# snowflake_insert.net
KiCad netlist of a schematic drawn in EAGLE
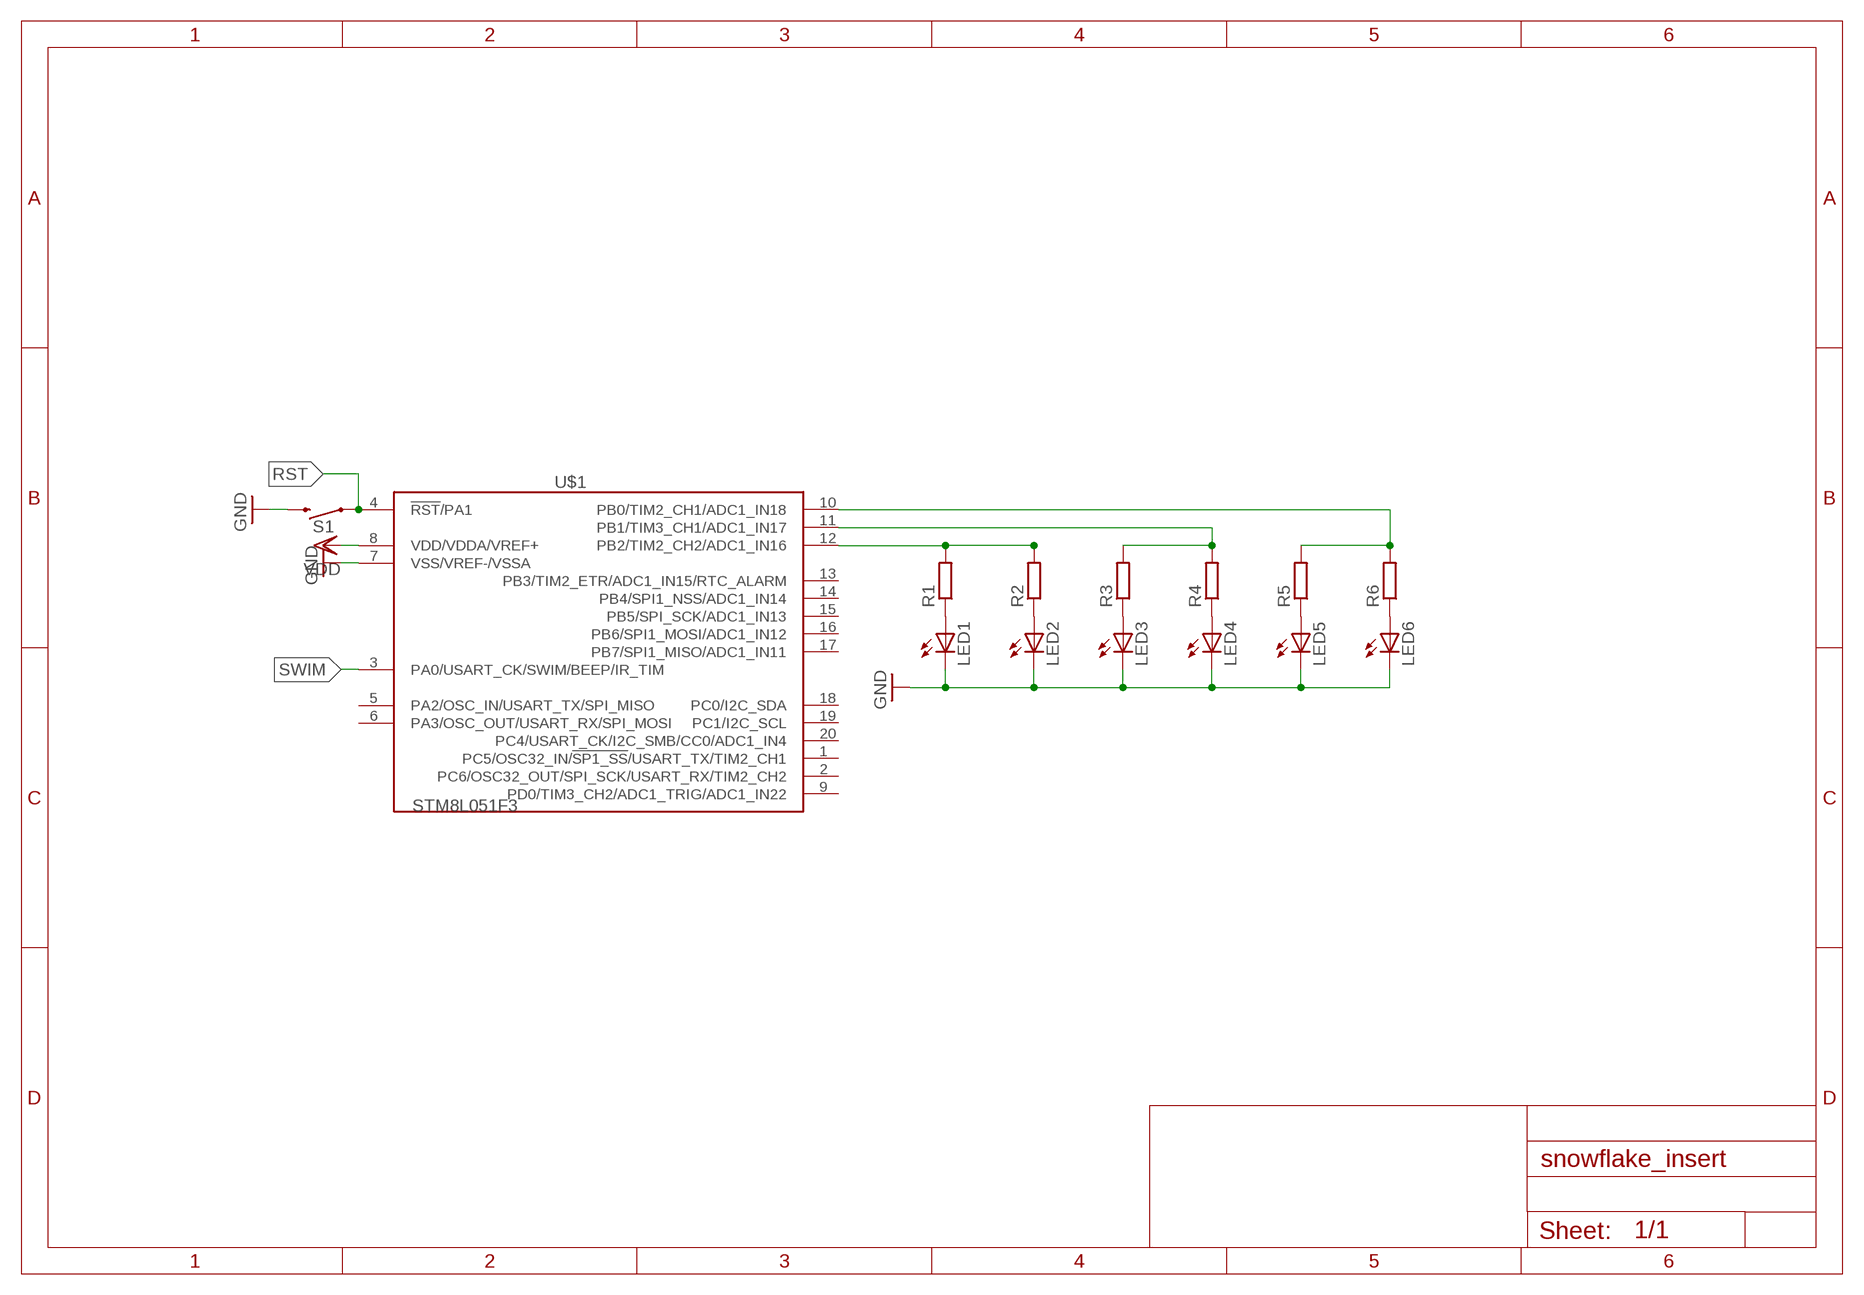
[diagram p0: schematic, sheet 1]

(export (version "E")
  (design (tool "Eeschema 10.0.6"))
  (components
    (comp (ref "LED1")
      (value "LEDSML0805")
      (footprint "eagle-import:SML0805")
      (libsource (lib "eagle-import") (part "LEDSML0805"))
    )
    (comp (ref "LED2")
      (value "LEDSML0805")
      (footprint "eagle-import:SML0805")
      (libsource (lib "eagle-import") (part "LEDSML0805"))
    )
    (comp (ref "LED3")
      (value "LEDSML0805")
      (footprint "eagle-import:SML0805")
      (libsource (lib "eagle-import") (part "LEDSML0805"))
    )
    (comp (ref "LED4")
      (value "LEDSML0805")
      (footprint "eagle-import:SML0805")
      (libsource (lib "eagle-import") (part "LEDSML0805"))
    )
    (comp (ref "LED5")
      (value "LEDSML0805")
      (footprint "eagle-import:SML0805")
      (libsource (lib "eagle-import") (part "LEDSML0805"))
    )
    (comp (ref "LED6")
      (value "LEDSML0805")
      (footprint "eagle-import:SML0805")
      (libsource (lib "eagle-import") (part "LEDSML0805"))
    )
    (comp (ref "R1")
      (value "R-EU_R0603")
      (footprint "eagle-import:R0603")
      (libsource (lib "eagle-import") (part "R-EU_R0603"))
    )
    (comp (ref "R2")
      (value "R-EU_R0603")
      (footprint "eagle-import:R0603")
      (libsource (lib "eagle-import") (part "R-EU_R0603"))
    )
    (comp (ref "R3")
      (value "R-EU_R0402")
      (footprint "eagle-import:R0402")
      (libsource (lib "eagle-import") (part "R-EU_R0402"))
    )
    (comp (ref "R4")
      (value "R-EU_R0603")
      (footprint "eagle-import:R0603")
      (libsource (lib "eagle-import") (part "R-EU_R0603"))
    )
    (comp (ref "R5")
      (value "R-EU_R0603")
      (footprint "eagle-import:R0603")
      (libsource (lib "eagle-import") (part "R-EU_R0603"))
    )
    (comp (ref "R6")
      (value "R-EU_R0603")
      (footprint "eagle-import:R0603")
      (libsource (lib "eagle-import") (part "R-EU_R0603"))
    )
    (comp (ref "S1")
      (value "MOMENTARY-SWITCH-SPST-SMD-6.0X3.5MM")
      (footprint "eagle-import:TACTILE_SWITCH_SMD_6.0X3.5MM")
      (libsource (lib "eagle-import") (part "MOMENTARY-SWITCH-SPST-SMD-6.0X3.5MM"))
    )
    (comp (ref "U$1")
      (value "STM8L051F3")
      (footprint "eagle-import:TSSOP20")
      (libsource (lib "eagle-import") (part "STM8L051F3"))
    )
  )
  (nets
    (net (code "1") (name "GND") (class "Default")
      (node (ref "LED1") (pin "C") (pinfunction "C_C") (pintype "passive"))
      (node (ref "LED2") (pin "C") (pinfunction "C_C") (pintype "passive"))
      (node (ref "LED3") (pin "C") (pinfunction "C_C") (pintype "passive"))
      (node (ref "LED4") (pin "C") (pinfunction "C_C") (pintype "passive"))
      (node (ref "LED5") (pin "C") (pinfunction "C_C") (pintype "passive"))
      (node (ref "LED6") (pin "C") (pinfunction "C_C") (pintype "passive"))
      (node (ref "S1") (pin "2") (pinfunction "2_2") (pintype "passive"))
      (node (ref "U$1") (pin "7") (pinfunction "VSS/VREF-/VSSA_7") (pintype "power_in"))
    )
    (net (code "2") (name "Net-(LED1-PadA)") (class "Default")
      (node (ref "LED1") (pin "A") (pinfunction "A_A") (pintype "passive"))
      (node (ref "R1") (pin "1") (pinfunction "1_1") (pintype "passive"))
    )
    (net (code "3") (name "Net-(LED2-PadA)") (class "Default")
      (node (ref "LED2") (pin "A") (pinfunction "A_A") (pintype "passive"))
      (node (ref "R2") (pin "1") (pinfunction "1_1") (pintype "passive"))
    )
    (net (code "4") (name "Net-(LED3-PadA)") (class "Default")
      (node (ref "LED3") (pin "A") (pinfunction "A_A") (pintype "passive"))
      (node (ref "R3") (pin "1") (pinfunction "1_1") (pintype "passive"))
    )
    (net (code "5") (name "Net-(LED4-PadA)") (class "Default")
      (node (ref "LED4") (pin "A") (pinfunction "A_A") (pintype "passive"))
      (node (ref "R4") (pin "1") (pinfunction "1_1") (pintype "passive"))
    )
    (net (code "6") (name "Net-(LED5-PadA)") (class "Default")
      (node (ref "LED5") (pin "A") (pinfunction "A_A") (pintype "passive"))
      (node (ref "R5") (pin "1") (pinfunction "1_1") (pintype "passive"))
    )
    (net (code "7") (name "Net-(LED6-PadA)") (class "Default")
      (node (ref "LED6") (pin "A") (pinfunction "A_A") (pintype "passive"))
      (node (ref "R6") (pin "1") (pinfunction "1_1") (pintype "passive"))
    )
    (net (code "8") (name "Net-(U$1-PB0{slash}TIM2_CH1{slash}ADC1_IN18)") (class "Default")
      (node (ref "R5") (pin "2") (pinfunction "2_2") (pintype "passive"))
      (node (ref "R6") (pin "2") (pinfunction "2_2") (pintype "passive"))
      (node (ref "U$1") (pin "10") (pinfunction "PB0/TIM2_CH1/ADC1_IN18_10") (pintype "bidirectional"))
    )
    (net (code "9") (name "Net-(U$1-PB1{slash}TIM3_CH1{slash}ADC1_IN17)") (class "Default")
      (node (ref "R3") (pin "2") (pinfunction "2_2") (pintype "passive"))
      (node (ref "R4") (pin "2") (pinfunction "2_2") (pintype "passive"))
      (node (ref "U$1") (pin "11") (pinfunction "PB1/TIM3_CH1/ADC1_IN17_11") (pintype "bidirectional"))
    )
    (net (code "10") (name "Net-(U$1-PB2{slash}TIM2_CH2{slash}ADC1_IN16)") (class "Default")
      (node (ref "R1") (pin "2") (pinfunction "2_2") (pintype "passive"))
      (node (ref "R2") (pin "2") (pinfunction "2_2") (pintype "passive"))
      (node (ref "U$1") (pin "12") (pinfunction "PB2/TIM2_CH2/ADC1_IN16_12") (pintype "bidirectional"))
    )
    (net (code "11") (name "RST") (class "Default")
      (node (ref "S1") (pin "1") (pinfunction "1_1") (pintype "passive"))
      (node (ref "U$1") (pin "4") (pinfunction "~{RST}/PA1_4") (pintype "input"))
    )
    (net (code "12") (name "SWIM") (class "Default")
      (node (ref "U$1") (pin "3") (pinfunction "PA0/USART_CK/SWIM/BEEP/IR_TIM_3") (pintype "power_in"))
    )
    (net (code "13") (name "VDD") (class "Default")
      (node (ref "U$1") (pin "8") (pinfunction "VDD/VDDA/VREF+_8") (pintype "power_in"))
    )
    (net (code "14") (name "unconnected-(U$1-PA2{slash}OSC_IN{slash}USART_TX{slash}SPI_MISO-Pad5)") (class "Default")
      (node (ref "U$1") (pin "5") (pinfunction "PA2/OSC_IN/USART_TX/SPI_MISO_5") (pintype "bidirectional"))
    )
    (net (code "15") (name "unconnected-(U$1-PA3{slash}OSC_OUT{slash}USART_RX{slash}SPI_MOSI-Pad6)") (class "Default")
      (node (ref "U$1") (pin "6") (pinfunction "PA3/OSC_OUT/USART_RX/SPI_MOSI_6") (pintype "bidirectional"))
    )
    (net (code "16") (name "unconnected-(U$1-PB3{slash}TIM2_ETR{slash}ADC1_IN15{slash}RTC_ALARM-Pad13)") (class "Default")
      (node (ref "U$1") (pin "13") (pinfunction "PB3/TIM2_ETR/ADC1_IN15/RTC_ALARM_13") (pintype "bidirectional"))
    )
    (net (code "17") (name "unconnected-(U$1-PB4{slash}SPI1_NSS{slash}ADC1_IN14-Pad14)") (class "Default")
      (node (ref "U$1") (pin "14") (pinfunction "PB4/SPI1_NSS/ADC1_IN14_14") (pintype "bidirectional"))
    )
    (net (code "18") (name "unconnected-(U$1-PB5{slash}SPI_SCK{slash}ADC1_IN13-Pad15)") (class "Default")
      (node (ref "U$1") (pin "15") (pinfunction "PB5/SPI_SCK/ADC1_IN13_15") (pintype "bidirectional"))
    )
    (net (code "19") (name "unconnected-(U$1-PB6{slash}SPI1_MOSI{slash}ADC1_IN12-Pad16)") (class "Default")
      (node (ref "U$1") (pin "16") (pinfunction "PB6/SPI1_MOSI/ADC1_IN12_16") (pintype "bidirectional"))
    )
    (net (code "20") (name "unconnected-(U$1-PB7{slash}SPI1_MISO{slash}ADC1_IN11-Pad17)") (class "Default")
      (node (ref "U$1") (pin "17") (pinfunction "PB7/SPI1_MISO/ADC1_IN11_17") (pintype "bidirectional"))
    )
    (net (code "21") (name "unconnected-(U$1-PC0{slash}I2C_SDA-Pad18)") (class "Default")
      (node (ref "U$1") (pin "18") (pinfunction "PC0/I2C_SDA_18") (pintype "bidirectional"))
    )
    (net (code "22") (name "unconnected-(U$1-PC1{slash}I2C_SCL-Pad19)") (class "Default")
      (node (ref "U$1") (pin "19") (pinfunction "PC1/I2C_SCL_19") (pintype "bidirectional"))
    )
    (net (code "23") (name "unconnected-(U$1-PC4{slash}USART_CK{slash}I2C_SMB{slash}CC0{slash}ADC1_IN4-Pad20)") (class "Default")
      (node (ref "U$1") (pin "20") (pinfunction "PC4/USART_CK/I2C_SMB/CC0/ADC1_IN4_20") (pintype "bidirectional"))
    )
    (net (code "24") (name "unconnected-(U$1-PC5{slash}OSC32_IN{slash}~{SP1_SS}{slash}USART_TX{slash}TIM2_CH1-Pad1)") (class "Default")
      (node (ref "U$1") (pin "1") (pinfunction "PC5/OSC32_IN/~{SP1_SS}/USART_TX/TIM2_CH1_1") (pintype "bidirectional"))
    )
    (net (code "25") (name "unconnected-(U$1-PC6{slash}OSC32_OUT{slash}SPI_SCK{slash}USART_RX{slash}TIM2_CH2-Pad2)") (class "Default")
      (node (ref "U$1") (pin "2") (pinfunction "PC6/OSC32_OUT/SPI_SCK/USART_RX/TIM2_CH2_2") (pintype "bidirectional"))
    )
    (net (code "26") (name "unconnected-(U$1-PD0{slash}TIM3_CH2{slash}ADC1_TRIG{slash}ADC1_IN22-Pad9)") (class "Default")
      (node (ref "U$1") (pin "9") (pinfunction "PD0/TIM3_CH2/ADC1_TRIG/ADC1_IN22_9") (pintype "bidirectional"))
    )
  )
)
